# Motortreiber_5_6.net
KiCad netlist of a schematic drawn in Altium Designer
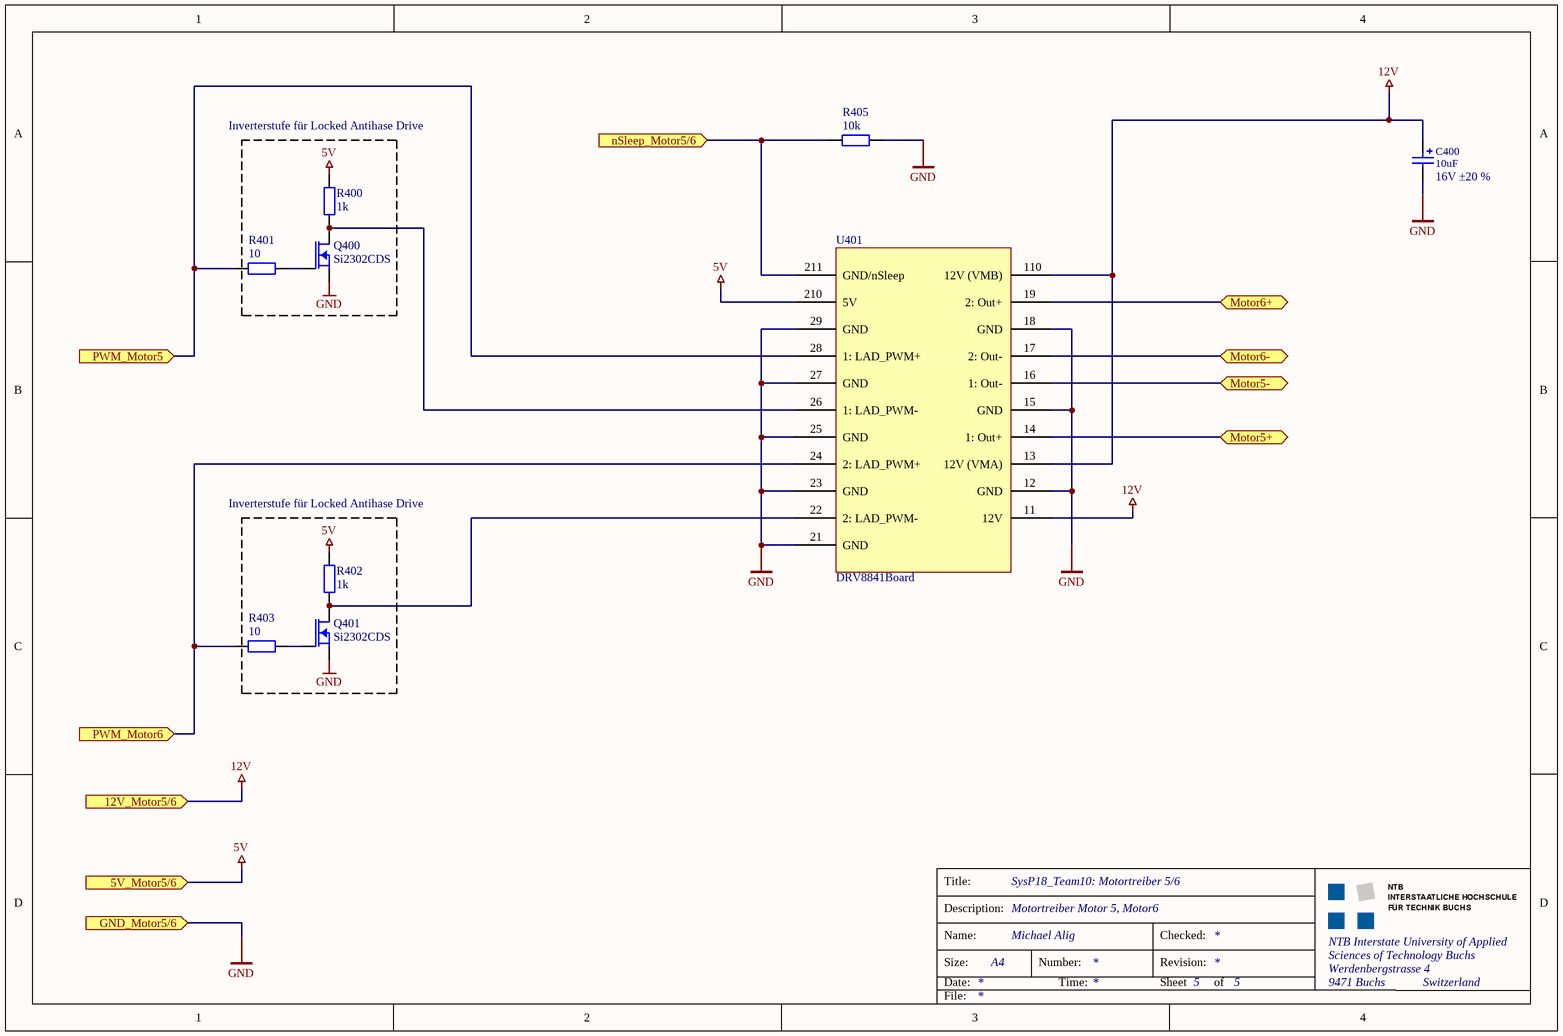
[diagram p0: Motortreiber_5,6.SchDoc]

(export (version "E")
  (design (tool "Eeschema 10.0.6"))
  (components
    (comp (ref "C400")
      (value "10uF")
      (footprint "CDE_CAP AVE CODE D_H")
      (description "Aluminum Electrolytic Capacitors for Filtering and Bypass, 47uF, 16V")
      (fields
        (field (name "MANUFACTURER") "Cornell Dubilier")
        (field (name "VALUEADDON") "16V ±20 %")
        (field (name "Comment") "AVE476M16D16T-F")
        (field (name "PUBLISHER") "Stefan Ursella, M.Eng")
      )
      (libsource (lib "Motorentreiber") (part "CDE_AVE476M16D16T-F_AVE CODE D"))
    )
    (comp (ref "Q400")
      (value "Si2302CDS")
      (footprint "SOT23-3")
      (description "N-Channel 20V (D-S) MOSFET")
      (libsource (lib "Motorentreiber") (part "Depletion Mode MOSFET"))
    )
    (comp (ref "Q401")
      (value "Si2302CDS")
      (footprint "SOT23-3")
      (description "N-Channel 20V (D-S) MOSFET")
      (libsource (lib "Motorentreiber") (part "Depletion Mode MOSFET"))
    )
    (comp (ref "R400")
      (value "1k")
      (footprint "GEN_R0805_H")
      (description "generic resistor")
      (fields
        (field (name "MANUFACTURER") "Tbd")
        (field (name "Comment") "Generic")
        (field (name "PUBLISHER") "Altium Limited")
      )
      (libsource (lib "Motorentreiber") (part "GEN_R_2"))
    )
    (comp (ref "R401")
      (value "10")
      (footprint "GEN_R0805_H")
      (description "generic resistor")
      (fields
        (field (name "MANUFACTURER") "Tbd")
        (field (name "Comment") "Generic")
        (field (name "PUBLISHER") "Altium Limited")
      )
      (libsource (lib "") (part "GEN_R_2_1"))
    )
    (comp (ref "R402")
      (value "1k")
      (footprint "GEN_R0805_H")
      (description "generic resistor")
      (fields
        (field (name "MANUFACTURER") "Tbd")
        (field (name "Comment") "Generic")
        (field (name "PUBLISHER") "Altium Limited")
      )
      (libsource (lib "Motorentreiber") (part "GEN_R_2"))
    )
    (comp (ref "R403")
      (value "10")
      (footprint "GEN_R0805_H")
      (description "generic resistor")
      (fields
        (field (name "MANUFACTURER") "Tbd")
        (field (name "Comment") "Generic")
        (field (name "PUBLISHER") "Altium Limited")
      )
      (libsource (lib "") (part "GEN_R_2_1"))
    )
    (comp (ref "R405")
      (value "10k")
      (footprint "GEN_R0805_H")
      (description "generic resistor")
      (fields
        (field (name "MANUFACTURER") "Tbd")
        (field (name "Comment") "Generic")
        (field (name "PUBLISHER") "Altium Limited")
      )
      (libsource (lib "") (part "GEN_R_2_1"))
    )
    (comp (ref "U401")
      (value "DRV8841Board")
      (footprint "DRV8841_Board")
      (libsource (lib "Motorentreiber") (part "DRV8841_Board"))
    )
  )
  (nets
    (net (code "1") (name "/Motor5+") (class "Default")
      (node (ref "U401") (pin "14") (pinfunction "1:_Out+_14") (pintype "passive"))
    )
    (net (code "2") (name "/Motor5-") (class "Default")
      (node (ref "U401") (pin "16") (pinfunction "1:_Out-_16") (pintype "passive"))
    )
    (net (code "3") (name "/Motor6+") (class "Default")
      (node (ref "U401") (pin "19") (pinfunction "2:_Out+_19") (pintype "passive"))
    )
    (net (code "4") (name "/Motor6-") (class "Default")
      (node (ref "U401") (pin "17") (pinfunction "2:_Out-_17") (pintype "passive"))
    )
    (net (code "5") (name "/PWM_Motor5") (class "Default")
      (node (ref "R401") (pin "1") (pinfunction "1_1") (pintype "passive"))
      (node (ref "U401") (pin "28") (pinfunction "1:_LAD_PWM+_28") (pintype "passive"))
    )
    (net (code "6") (name "/PWM_Motor6") (class "Default")
      (node (ref "R403") (pin "1") (pinfunction "1_1") (pintype "passive"))
      (node (ref "U401") (pin "24") (pinfunction "2:_LAD_PWM+_24") (pintype "passive"))
    )
    (net (code "7") (name "/nSleep_Motor5{slash}6") (class "Default")
      (node (ref "R405") (pin "1") (pinfunction "1_1") (pintype "passive"))
      (node (ref "U401") (pin "211") (pinfunction "GND/nSleep_211") (pintype "passive"))
    )
    (net (code "8") (name "5V") (class "Default")
      (node (ref "R400") (pin "2") (pinfunction "2_2") (pintype "passive"))
      (node (ref "R402") (pin "2") (pinfunction "2_2") (pintype "passive"))
      (node (ref "U401") (pin "210") (pinfunction "5V_210") (pintype "passive"))
    )
    (net (code "9") (name "12V") (class "Default")
      (node (ref "C400") (pin "1") (pinfunction "Pos_1") (pintype "passive"))
      (node (ref "U401") (pin "11") (pinfunction "12V_11") (pintype "passive"))
      (node (ref "U401") (pin "110") (pinfunction "12V_(VMB)_110") (pintype "passive"))
      (node (ref "U401") (pin "13") (pinfunction "12V_(VMA)_13") (pintype "passive"))
    )
    (net (code "10") (name "GND") (class "Default")
      (node (ref "C400") (pin "2") (pinfunction "Neg_2") (pintype "passive"))
      (node (ref "Q400") (pin "2") (pinfunction "S_2") (pintype "passive"))
      (node (ref "Q401") (pin "2") (pinfunction "S_2") (pintype "passive"))
      (node (ref "R405") (pin "2") (pinfunction "2_2") (pintype "passive"))
      (node (ref "U401") (pin "12") (pinfunction "GND_12") (pintype "passive"))
      (node (ref "U401") (pin "15") (pinfunction "GND_15") (pintype "passive"))
      (node (ref "U401") (pin "18") (pinfunction "GND_18") (pintype "passive"))
      (node (ref "U401") (pin "21") (pinfunction "GND_21") (pintype "passive"))
      (node (ref "U401") (pin "23") (pinfunction "GND_23") (pintype "passive"))
      (node (ref "U401") (pin "25") (pinfunction "GND_25") (pintype "passive"))
      (node (ref "U401") (pin "27") (pinfunction "GND_27") (pintype "passive"))
      (node (ref "U401") (pin "29") (pinfunction "GND_29") (pintype "passive"))
    )
    (net (code "11") (name "Net-(Q400-D)") (class "Default")
      (node (ref "Q400") (pin "3") (pinfunction "D_3") (pintype "passive"))
      (node (ref "R400") (pin "1") (pinfunction "1_1") (pintype "passive"))
      (node (ref "U401") (pin "26") (pinfunction "1:_LAD_PWM-_26") (pintype "passive"))
    )
    (net (code "12") (name "Net-(Q400-G)") (class "Default")
      (node (ref "Q400") (pin "1") (pinfunction "G_1") (pintype "passive"))
      (node (ref "R401") (pin "2") (pinfunction "2_2") (pintype "passive"))
    )
    (net (code "13") (name "Net-(Q401-D)") (class "Default")
      (node (ref "Q401") (pin "3") (pinfunction "D_3") (pintype "passive"))
      (node (ref "R402") (pin "1") (pinfunction "1_1") (pintype "passive"))
      (node (ref "U401") (pin "22") (pinfunction "2:_LAD_PWM-_22") (pintype "passive"))
    )
    (net (code "14") (name "Net-(Q401-G)") (class "Default")
      (node (ref "Q401") (pin "1") (pinfunction "G_1") (pintype "passive"))
      (node (ref "R403") (pin "2") (pinfunction "2_2") (pintype "passive"))
    )
  )
)
